# bump-sensor.net
KiCad netlist of a schematic drawn in EAGLE
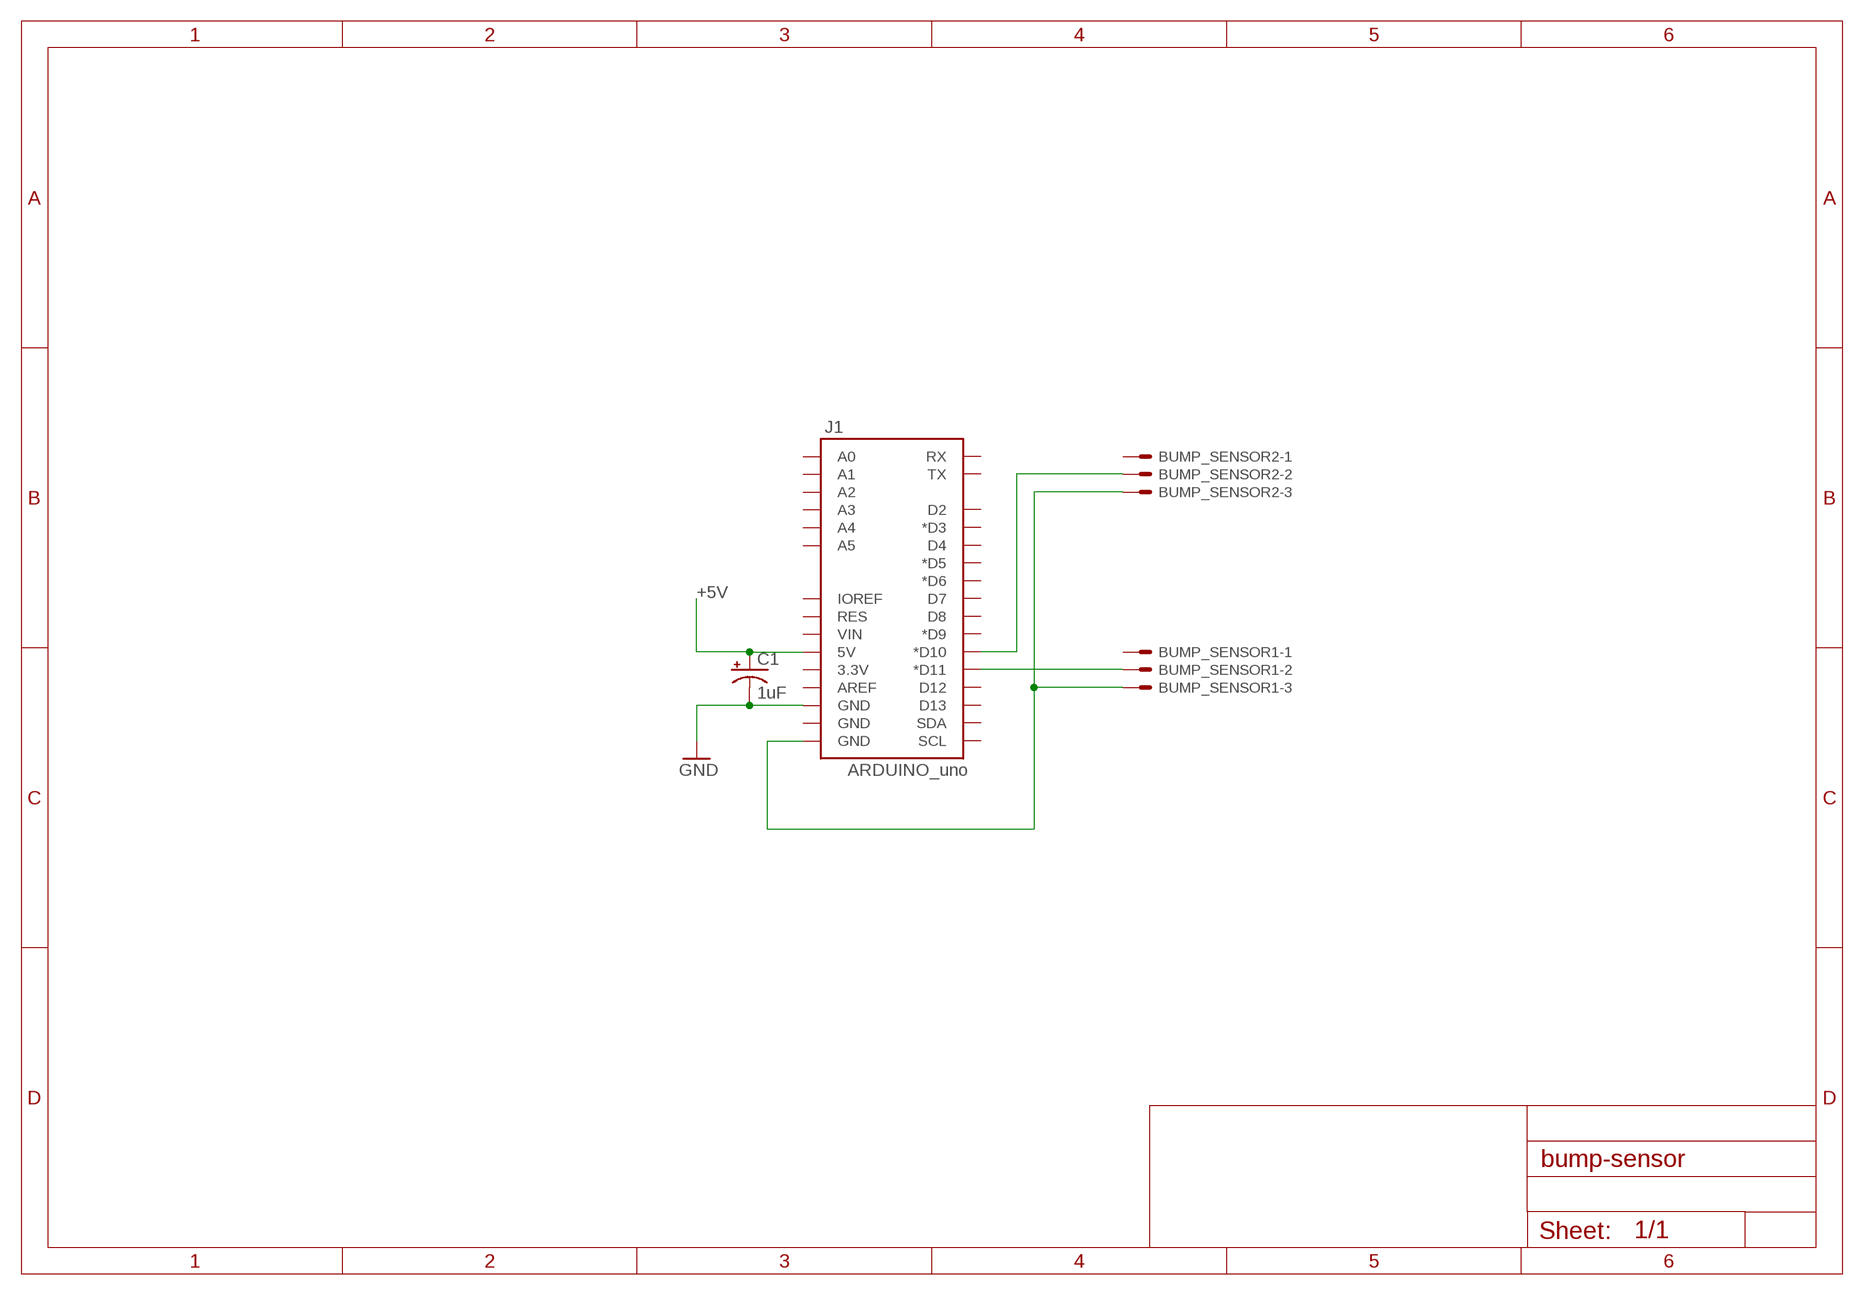
[diagram p0: schematic, sheet 1]

(export (version "E")
  (design (tool "Eeschema 10.0.6"))
  (components
    (comp (ref "BUMP_SENSOR1")
      (value "22-23-2031")
      (footprint "eagle-import:22-23-2031")
      (fields (field (name "MF") "MOLEX"))
      (libsource (lib "eagle-import") (part "22-23-2031"))
    )
    (comp (ref "BUMP_SENSOR2")
      (value "22-23-2031")
      (footprint "eagle-import:22-23-2031")
      (fields (field (name "MF") "MOLEX"))
      (libsource (lib "eagle-import") (part "22-23-2031"))
    )
    (comp (ref "C1")
      (value "1uF")
      (footprint "eagle-import:EIA3216")
      (libsource (lib "eagle-import") (part "CAP_POL1206"))
    )
    (comp (ref "J1")
      (value "ARDUINO_uno")
      (footprint "eagle-import:UNO_R3_SHIELD")
      (libsource (lib "eagle-import") (part "ARDUINO_R3_SHIELD"))
    )
  )
  (nets
    (net (code "1") (name "/+5V") (class "Default")
      (node (ref "C1") (pin "A") (pinfunction "+_A") (pintype "passive"))
      (node (ref "J1") (pin "5V") (pinfunction "5V_5V") (pintype "bidirectional"))
    )
    (net (code "2") (name "GND") (class "Default")
      (node (ref "C1") (pin "C") (pinfunction "-_C") (pintype "passive"))
      (node (ref "J1") (pin "GND@2") (pinfunction "GND_GND@2") (pintype "bidirectional"))
    )
    (net (code "3") (name "Net-(BUMP_SENSOR1B-S)") (class "Default")
      (node (ref "BUMP_SENSOR1") (pin "2") (pinfunction "S_2") (pintype "passive"))
      (node (ref "J1") (pin "D11") (pinfunction "*D11_D11") (pintype "bidirectional"))
    )
    (net (code "4") (name "Net-(BUMP_SENSOR1C-S)") (class "Default")
      (node (ref "BUMP_SENSOR1") (pin "3") (pinfunction "S_3") (pintype "passive"))
      (node (ref "BUMP_SENSOR2") (pin "3") (pinfunction "S_3") (pintype "passive"))
      (node (ref "J1") (pin "GND@0") (pinfunction "GND_GND@0") (pintype "bidirectional"))
    )
    (net (code "5") (name "Net-(BUMP_SENSOR2B-S)") (class "Default")
      (node (ref "BUMP_SENSOR2") (pin "2") (pinfunction "S_2") (pintype "passive"))
      (node (ref "J1") (pin "D10") (pinfunction "*D10_D10") (pintype "bidirectional"))
    )
    (net (code "6") (name "unconnected-(BUMP_SENSOR1A-S-Pad1)") (class "Default")
      (node (ref "BUMP_SENSOR1") (pin "1") (pinfunction "S_1") (pintype "passive"))
    )
    (net (code "7") (name "unconnected-(BUMP_SENSOR2A-S-Pad1)") (class "Default")
      (node (ref "BUMP_SENSOR2") (pin "1") (pinfunction "S_1") (pintype "passive"))
    )
    (net (code "8") (name "unconnected-(J1-*D3-PadD3)") (class "Default")
      (node (ref "J1") (pin "D3") (pinfunction "*D3_D3") (pintype "bidirectional"))
    )
    (net (code "9") (name "unconnected-(J1-*D5-PadD5)") (class "Default")
      (node (ref "J1") (pin "D5") (pinfunction "*D5_D5") (pintype "bidirectional"))
    )
    (net (code "10") (name "unconnected-(J1-*D6-PadD6)") (class "Default")
      (node (ref "J1") (pin "D6") (pinfunction "*D6_D6") (pintype "bidirectional"))
    )
    (net (code "11") (name "unconnected-(J1-*D9-PadD9)") (class "Default")
      (node (ref "J1") (pin "D9") (pinfunction "*D9_D9") (pintype "bidirectional"))
    )
    (net (code "12") (name "unconnected-(J1-GND-PadGND@1)") (class "Default")
      (node (ref "J1") (pin "GND@1") (pinfunction "GND_GND@1") (pintype "bidirectional"))
    )
    (net (code "13") (name "unconnected-(J1-Pad3.3V)") (class "Default")
      (node (ref "J1") (pin "3.3V") (pinfunction "3.3V_3.3V") (pintype "bidirectional"))
    )
    (net (code "14") (name "unconnected-(J1-PadA0)") (class "Default")
      (node (ref "J1") (pin "A0") (pinfunction "A0_A0") (pintype "bidirectional"))
    )
    (net (code "15") (name "unconnected-(J1-PadA1)") (class "Default")
      (node (ref "J1") (pin "A1") (pinfunction "A1_A1") (pintype "bidirectional"))
    )
    (net (code "16") (name "unconnected-(J1-PadA2)") (class "Default")
      (node (ref "J1") (pin "A2") (pinfunction "A2_A2") (pintype "bidirectional"))
    )
    (net (code "17") (name "unconnected-(J1-PadA3)") (class "Default")
      (node (ref "J1") (pin "A3") (pinfunction "A3_A3") (pintype "bidirectional"))
    )
    (net (code "18") (name "unconnected-(J1-PadA4)") (class "Default")
      (node (ref "J1") (pin "A4") (pinfunction "A4_A4") (pintype "bidirectional"))
    )
    (net (code "19") (name "unconnected-(J1-PadA5)") (class "Default")
      (node (ref "J1") (pin "A5") (pinfunction "A5_A5") (pintype "bidirectional"))
    )
    (net (code "20") (name "unconnected-(J1-PadAREF)") (class "Default")
      (node (ref "J1") (pin "AREF") (pinfunction "AREF_AREF") (pintype "bidirectional"))
    )
    (net (code "21") (name "unconnected-(J1-PadD2)") (class "Default")
      (node (ref "J1") (pin "D2") (pinfunction "D2_D2") (pintype "bidirectional"))
    )
    (net (code "22") (name "unconnected-(J1-PadD4)") (class "Default")
      (node (ref "J1") (pin "D4") (pinfunction "D4_D4") (pintype "bidirectional"))
    )
    (net (code "23") (name "unconnected-(J1-PadD7)") (class "Default")
      (node (ref "J1") (pin "D7") (pinfunction "D7_D7") (pintype "bidirectional"))
    )
    (net (code "24") (name "unconnected-(J1-PadD8)") (class "Default")
      (node (ref "J1") (pin "D8") (pinfunction "D8_D8") (pintype "bidirectional"))
    )
    (net (code "25") (name "unconnected-(J1-PadD12)") (class "Default")
      (node (ref "J1") (pin "D12") (pinfunction "D12_D12") (pintype "bidirectional"))
    )
    (net (code "26") (name "unconnected-(J1-PadD13)") (class "Default")
      (node (ref "J1") (pin "D13") (pinfunction "D13_D13") (pintype "bidirectional"))
    )
    (net (code "27") (name "unconnected-(J1-PadIOREF)") (class "Default")
      (node (ref "J1") (pin "IOREF") (pinfunction "IOREF_IOREF") (pintype "bidirectional"))
    )
    (net (code "28") (name "unconnected-(J1-PadRES)") (class "Default")
      (node (ref "J1") (pin "RES") (pinfunction "RES_RES") (pintype "bidirectional"))
    )
    (net (code "29") (name "unconnected-(J1-PadRX)") (class "Default")
      (node (ref "J1") (pin "RX") (pinfunction "RX_RX") (pintype "bidirectional"))
    )
    (net (code "30") (name "unconnected-(J1-PadSCL)") (class "Default")
      (node (ref "J1") (pin "SCL") (pinfunction "SCL_SCL") (pintype "bidirectional"))
    )
    (net (code "31") (name "unconnected-(J1-PadSDA)") (class "Default")
      (node (ref "J1") (pin "SDA") (pinfunction "SDA_SDA") (pintype "bidirectional"))
    )
    (net (code "32") (name "unconnected-(J1-PadTX)") (class "Default")
      (node (ref "J1") (pin "TX") (pinfunction "TX_TX") (pintype "bidirectional"))
    )
    (net (code "33") (name "unconnected-(J1-PadVIN)") (class "Default")
      (node (ref "J1") (pin "VIN") (pinfunction "VIN_VIN") (pintype "bidirectional"))
    )
  )
)
